# USBPower.net
KiCad netlist of a schematic drawn in Altium Designer
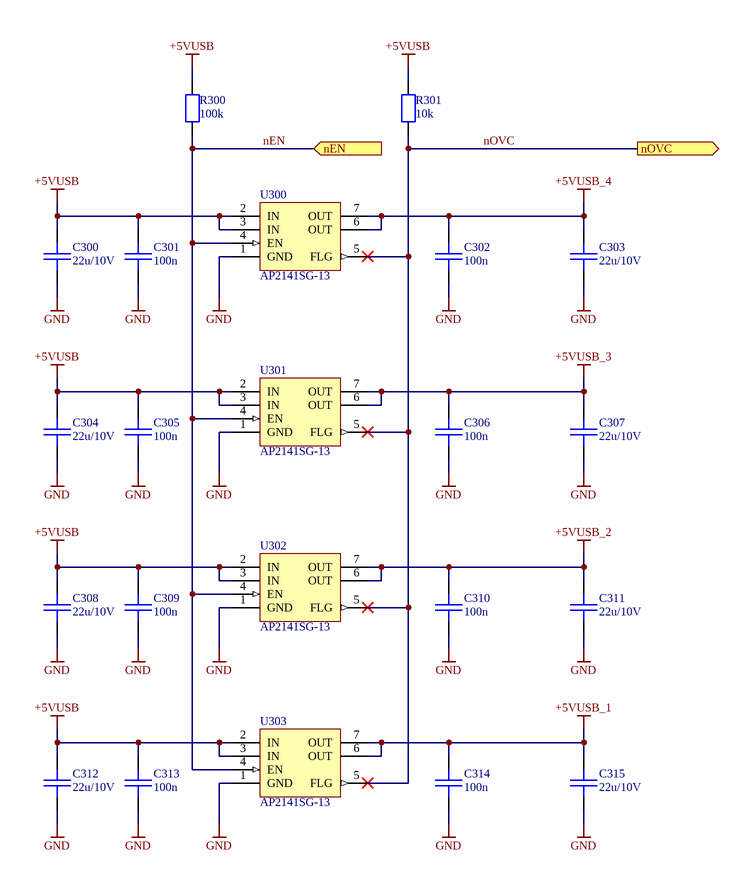
[diagram p0: USBPower.SchDoc]

(export (version "E")
  (design (tool "Eeschema 10.0.6"))
  (components
    (comp (ref "C300")
      (value "22u/10V")
      (footprint "0805_C_E0")
      (description "Chip capacitor, generic")
      (libsource (lib "CyberDeck") (part "C"))
    )
    (comp (ref "C301")
      (value "100n")
      (footprint "0603_C")
      (description "Chip capacitor, generic")
      (libsource (lib "CyberDeck") (part "C"))
    )
    (comp (ref "C302")
      (value "100n")
      (footprint "0603_C")
      (description "Chip capacitor, generic")
      (libsource (lib "CyberDeck") (part "C"))
    )
    (comp (ref "C303")
      (value "22u/10V")
      (footprint "0805_C_E0")
      (description "Chip capacitor, generic")
      (libsource (lib "CyberDeck") (part "C"))
    )
    (comp (ref "C304")
      (value "22u/10V")
      (footprint "0805_C_E0")
      (description "Chip capacitor, generic")
      (libsource (lib "CyberDeck") (part "C"))
    )
    (comp (ref "C305")
      (value "100n")
      (footprint "0603_C")
      (description "Chip capacitor, generic")
      (libsource (lib "CyberDeck") (part "C"))
    )
    (comp (ref "C306")
      (value "100n")
      (footprint "0603_C")
      (description "Chip capacitor, generic")
      (libsource (lib "CyberDeck") (part "C"))
    )
    (comp (ref "C307")
      (value "22u/10V")
      (footprint "0805_C_E0")
      (description "Chip capacitor, generic")
      (libsource (lib "CyberDeck") (part "C"))
    )
    (comp (ref "C308")
      (value "22u/10V")
      (footprint "0805_C_E0")
      (description "Chip capacitor, generic")
      (libsource (lib "CyberDeck") (part "C"))
    )
    (comp (ref "C309")
      (value "100n")
      (footprint "0603_C")
      (description "Chip capacitor, generic")
      (libsource (lib "CyberDeck") (part "C"))
    )
    (comp (ref "C310")
      (value "100n")
      (footprint "0603_C")
      (description "Chip capacitor, generic")
      (libsource (lib "CyberDeck") (part "C"))
    )
    (comp (ref "C311")
      (value "22u/10V")
      (footprint "0805_C_E0")
      (description "Chip capacitor, generic")
      (libsource (lib "CyberDeck") (part "C"))
    )
    (comp (ref "C312")
      (value "22u/10V")
      (footprint "0805_C_E0")
      (description "Chip capacitor, generic")
      (libsource (lib "CyberDeck") (part "C"))
    )
    (comp (ref "C313")
      (value "100n")
      (footprint "0603_C")
      (description "Chip capacitor, generic")
      (libsource (lib "CyberDeck") (part "C"))
    )
    (comp (ref "C314")
      (value "100n")
      (footprint "0603_C")
      (description "Chip capacitor, generic")
      (libsource (lib "CyberDeck") (part "C"))
    )
    (comp (ref "C315")
      (value "22u/10V")
      (footprint "0805_C_E0")
      (description "Chip capacitor, generic")
      (libsource (lib "CyberDeck") (part "C"))
    )
    (comp (ref "R300")
      (value "100k")
      (footprint "0603_R")
      (description "Resistor, generic")
      (libsource (lib "CyberDeck") (part "R"))
    )
    (comp (ref "R301")
      (value "10k")
      (footprint "0603_R")
      (description "Resistor, generic")
      (libsource (lib "CyberDeck") (part "R"))
    )
    (comp (ref "U300")
      (value "AP2141SG-13")
      (footprint "SO8")
      (description "0.5A SINGLE CHANNEL CURRENT-LIMITED POWERSWITCH SOIC8")
      (fields (field (name "MANUFACTURER") "Diodes") (field (name "VOLTAGE") "5.5V"))
      (libsource (lib "Cyberdeck") (part "U_Q_AP2141SG-13"))
    )
    (comp (ref "U301")
      (value "AP2141SG-13")
      (footprint "SO8")
      (description "0.5A SINGLE CHANNEL CURRENT-LIMITED POWERSWITCH SOIC8")
      (fields (field (name "MANUFACTURER") "Diodes") (field (name "VOLTAGE") "5.5V"))
      (libsource (lib "Cyberdeck") (part "U_Q_AP2141SG-13"))
    )
    (comp (ref "U302")
      (value "AP2141SG-13")
      (footprint "SO8")
      (description "0.5A SINGLE CHANNEL CURRENT-LIMITED POWERSWITCH SOIC8")
      (fields (field (name "MANUFACTURER") "Diodes") (field (name "VOLTAGE") "5.5V"))
      (libsource (lib "Cyberdeck") (part "U_Q_AP2141SG-13"))
    )
    (comp (ref "U303")
      (value "AP2141SG-13")
      (footprint "SO8")
      (description "0.5A SINGLE CHANNEL CURRENT-LIMITED POWERSWITCH SOIC8")
      (fields (field (name "MANUFACTURER") "Diodes") (field (name "VOLTAGE") "5.5V"))
      (libsource (lib "Cyberdeck") (part "U_Q_AP2141SG-13"))
    )
  )
  (nets
    (net (code "1") (name "+5VUSB") (class "Default")
      (node (ref "C300") (pin "2") (pinfunction "2_2") (pintype "passive"))
      (node (ref "C301") (pin "2") (pinfunction "2_2") (pintype "passive"))
      (node (ref "C304") (pin "2") (pinfunction "2_2") (pintype "passive"))
      (node (ref "C305") (pin "2") (pinfunction "2_2") (pintype "passive"))
      (node (ref "C308") (pin "2") (pinfunction "2_2") (pintype "passive"))
      (node (ref "C309") (pin "2") (pinfunction "2_2") (pintype "passive"))
      (node (ref "C312") (pin "2") (pinfunction "2_2") (pintype "passive"))
      (node (ref "C313") (pin "2") (pinfunction "2_2") (pintype "passive"))
      (node (ref "R300") (pin "2") (pinfunction "2_2") (pintype "passive"))
      (node (ref "R301") (pin "2") (pinfunction "2_2") (pintype "passive"))
      (node (ref "U300") (pin "2") (pinfunction "IN_2") (pintype "power_in"))
      (node (ref "U300") (pin "3") (pinfunction "IN_3") (pintype "power_in"))
      (node (ref "U301") (pin "2") (pinfunction "IN_2") (pintype "power_in"))
      (node (ref "U301") (pin "3") (pinfunction "IN_3") (pintype "power_in"))
      (node (ref "U302") (pin "2") (pinfunction "IN_2") (pintype "power_in"))
      (node (ref "U302") (pin "3") (pinfunction "IN_3") (pintype "power_in"))
      (node (ref "U303") (pin "2") (pinfunction "IN_2") (pintype "power_in"))
      (node (ref "U303") (pin "3") (pinfunction "IN_3") (pintype "power_in"))
    )
    (net (code "2") (name "+5VUSB_1") (class "Default")
      (node (ref "C314") (pin "2") (pinfunction "2_2") (pintype "passive"))
      (node (ref "C315") (pin "2") (pinfunction "2_2") (pintype "passive"))
      (node (ref "U303") (pin "6") (pinfunction "OUT_6") (pintype "power_in"))
      (node (ref "U303") (pin "7") (pinfunction "OUT_7") (pintype "power_in"))
    )
    (net (code "3") (name "+5VUSB_2") (class "Default")
      (node (ref "C310") (pin "2") (pinfunction "2_2") (pintype "passive"))
      (node (ref "C311") (pin "2") (pinfunction "2_2") (pintype "passive"))
      (node (ref "U302") (pin "6") (pinfunction "OUT_6") (pintype "power_in"))
      (node (ref "U302") (pin "7") (pinfunction "OUT_7") (pintype "power_in"))
    )
    (net (code "4") (name "+5VUSB_3") (class "Default")
      (node (ref "C306") (pin "2") (pinfunction "2_2") (pintype "passive"))
      (node (ref "C307") (pin "2") (pinfunction "2_2") (pintype "passive"))
      (node (ref "U301") (pin "6") (pinfunction "OUT_6") (pintype "power_in"))
      (node (ref "U301") (pin "7") (pinfunction "OUT_7") (pintype "power_in"))
    )
    (net (code "5") (name "+5VUSB_4") (class "Default")
      (node (ref "C302") (pin "2") (pinfunction "2_2") (pintype "passive"))
      (node (ref "C303") (pin "2") (pinfunction "2_2") (pintype "passive"))
      (node (ref "U300") (pin "6") (pinfunction "OUT_6") (pintype "power_in"))
      (node (ref "U300") (pin "7") (pinfunction "OUT_7") (pintype "power_in"))
    )
    (net (code "6") (name "/nEN") (class "Default")
      (node (ref "R300") (pin "1") (pinfunction "1_1") (pintype "passive"))
      (node (ref "U300") (pin "4") (pinfunction "EN_4") (pintype "input"))
      (node (ref "U301") (pin "4") (pinfunction "EN_4") (pintype "input"))
      (node (ref "U302") (pin "4") (pinfunction "EN_4") (pintype "input"))
      (node (ref "U303") (pin "4") (pinfunction "EN_4") (pintype "input"))
    )
    (net (code "7") (name "/nOVC") (class "Default")
      (node (ref "R301") (pin "1") (pinfunction "1_1") (pintype "passive"))
      (node (ref "U300") (pin "5") (pinfunction "FLG_5") (pintype "output"))
      (node (ref "U301") (pin "5") (pinfunction "FLG_5") (pintype "output"))
      (node (ref "U302") (pin "5") (pinfunction "FLG_5") (pintype "output"))
      (node (ref "U303") (pin "5") (pinfunction "FLG_5") (pintype "output"))
    )
    (net (code "8") (name "GND") (class "Default")
      (node (ref "C300") (pin "1") (pinfunction "1_1") (pintype "passive"))
      (node (ref "C301") (pin "1") (pinfunction "1_1") (pintype "passive"))
      (node (ref "C302") (pin "1") (pinfunction "1_1") (pintype "passive"))
      (node (ref "C303") (pin "1") (pinfunction "1_1") (pintype "passive"))
      (node (ref "C304") (pin "1") (pinfunction "1_1") (pintype "passive"))
      (node (ref "C305") (pin "1") (pinfunction "1_1") (pintype "passive"))
      (node (ref "C306") (pin "1") (pinfunction "1_1") (pintype "passive"))
      (node (ref "C307") (pin "1") (pinfunction "1_1") (pintype "passive"))
      (node (ref "C308") (pin "1") (pinfunction "1_1") (pintype "passive"))
      (node (ref "C309") (pin "1") (pinfunction "1_1") (pintype "passive"))
      (node (ref "C310") (pin "1") (pinfunction "1_1") (pintype "passive"))
      (node (ref "C311") (pin "1") (pinfunction "1_1") (pintype "passive"))
      (node (ref "C312") (pin "1") (pinfunction "1_1") (pintype "passive"))
      (node (ref "C313") (pin "1") (pinfunction "1_1") (pintype "passive"))
      (node (ref "C314") (pin "1") (pinfunction "1_1") (pintype "passive"))
      (node (ref "C315") (pin "1") (pinfunction "1_1") (pintype "passive"))
      (node (ref "U300") (pin "1") (pinfunction "GND_1") (pintype "power_in"))
      (node (ref "U301") (pin "1") (pinfunction "GND_1") (pintype "power_in"))
      (node (ref "U302") (pin "1") (pinfunction "GND_1") (pintype "power_in"))
      (node (ref "U303") (pin "1") (pinfunction "GND_1") (pintype "power_in"))
    )
  )
)
